# design.net
KiCad netlist of a schematic drawn in Altium Designer
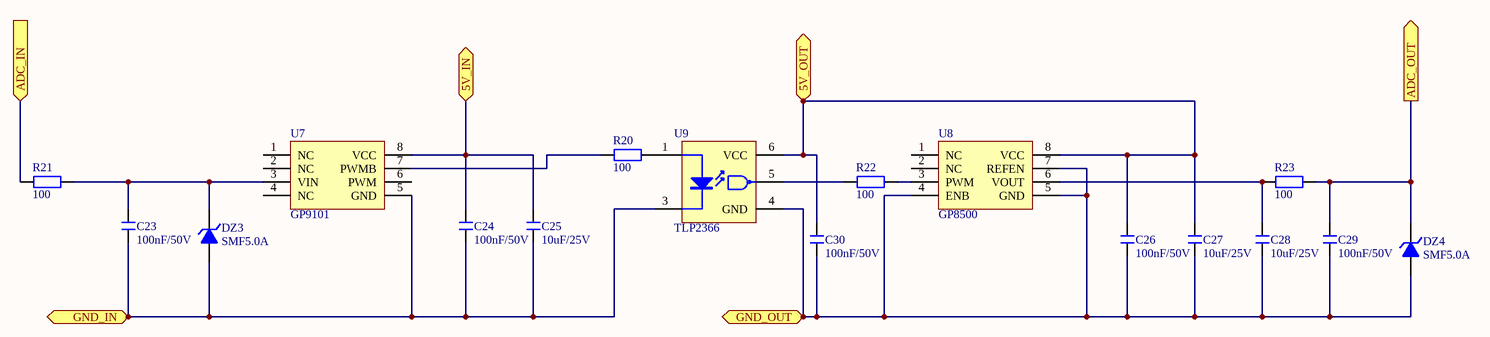
[diagram p0: 第二路电压隔离原理图.SchDoc]

(export (version "E")
  (design (tool "Eeschema 10.0.6"))
  (components
    (comp (ref "C23")
      (value "100nF/50V")
      (footprint "C 0603_M")
      (description "无极性贴片电容")
      (fields (field (name "版权归属") "源创客"))
      (libsource (lib "3.1   - 电阻-电容-电感") (part "C"))
    )
    (comp (ref "C24")
      (value "100nF/50V")
      (footprint "C 0603_M")
      (description "无极性贴片电容")
      (fields (field (name "版权归属") "源创客"))
      (libsource (lib "3.1   - 电阻-电容-电感") (part "C"))
    )
    (comp (ref "C25")
      (value "10uF/25V")
      (footprint "C 0603_M")
      (description "无极性贴片电容")
      (fields (field (name "版权归属") "源创客"))
      (libsource (lib "3.1   - 电阻-电容-电感") (part "C"))
    )
    (comp (ref "C26")
      (value "100nF/50V")
      (footprint "C 0603_M")
      (description "无极性贴片电容")
      (fields (field (name "版权归属") "源创客"))
      (libsource (lib "3.1   - 电阻-电容-电感") (part "C"))
    )
    (comp (ref "C27")
      (value "10uF/25V")
      (footprint "C 0603_M")
      (description "无极性贴片电容")
      (fields (field (name "版权归属") "源创客"))
      (libsource (lib "3.1   - 电阻-电容-电感") (part "C"))
    )
    (comp (ref "C28")
      (value "10uF/25V")
      (footprint "C 0603_M")
      (description "无极性贴片电容")
      (fields (field (name "版权归属") "源创客"))
      (libsource (lib "3.1   - 电阻-电容-电感") (part "C"))
    )
    (comp (ref "C29")
      (value "100nF/50V")
      (footprint "C 0603_M")
      (description "无极性贴片电容")
      (fields (field (name "版权归属") "源创客"))
      (libsource (lib "3.1   - 电阻-电容-电感") (part "C"))
    )
    (comp (ref "C30")
      (value "100nF/50V")
      (footprint "C 0603_M")
      (description "无极性贴片电容")
      (fields (field (name "版权归属") "源创客"))
      (libsource (lib "3.1   - 电阻-电容-电感") (part "C"))
    )
    (comp (ref "DZ3")
      (value "SMF5.0A")
      (footprint "SOD-123")
      (description "3.3V/0.5W稳压管")
      (fields (field (name "版权归属") "源创客"))
      (libsource (lib "8.1   - 二极管-整流桥") (part "1N4620"))
    )
    (comp (ref "DZ4")
      (value "SMF5.0A")
      (footprint "SOD-123")
      (description "3.3V/0.5W稳压管")
      (fields (field (name "版权归属") "源创客"))
      (libsource (lib "8.1   - 二极管-整流桥") (part "1N4620"))
    )
    (comp (ref "R20")
      (value "100")
      (footprint "R 0603_M")
      (description "贴片电阻")
      (fields (field (name "版权归属") "源创客"))
      (libsource (lib "3.1   - 电阻-电容-电感") (part "R"))
    )
    (comp (ref "R21")
      (value "100")
      (footprint "R 0603_M")
      (description "贴片电阻")
      (fields (field (name "版权归属") "源创客"))
      (libsource (lib "3.1   - 电阻-电容-电感") (part "R"))
    )
    (comp (ref "R22")
      (value "100")
      (footprint "R 0603_M")
      (description "贴片电阻")
      (fields (field (name "版权归属") "源创客"))
      (libsource (lib "3.1   - 电阻-电容-电感") (part "R"))
    )
    (comp (ref "R23")
      (value "100")
      (footprint "R 0603_M")
      (description "贴片电阻")
      (fields (field (name "版权归属") "源创客"))
      (libsource (lib "3.1   - 电阻-电容-电感") (part "R"))
    )
    (comp (ref "U7")
      (value "GP9101")
      (footprint "SOP8_N")
      (description "将0V到VCC的模拟电压输入，线性转换成0%-100%占  空比的PWM信号输出")
      (libsource (lib "1.1   - IC芯片") (part "GP9101"))
    )
    (comp (ref "U8")
      (value "GP8500")
      (footprint "SOP8_N")
      (description "0%-100% PWM 转 0-2.5V/0-VCC")
      (libsource (lib "1.1   - IC芯片") (part "GP8500"))
    )
    (comp (ref "U9")
      (value "TLP2366")
      (footprint "SOP5_N")
      (description "单路高速光耦")
      (libsource (lib "11.1 - 传感元件") (part "TLP2366"))
    )
  )
  (nets
    (net (code "1") (name "/5V_IN") (class "Default")
      (node (ref "C24") (pin "2") (pinfunction "2_2") (pintype "passive"))
      (node (ref "C25") (pin "2") (pinfunction "2_2") (pintype "passive"))
      (node (ref "U7") (pin "8") (pinfunction "VCC_8") (pintype "passive"))
    )
    (net (code "2") (name "/5V_OUT") (class "Default")
      (node (ref "C26") (pin "2") (pinfunction "2_2") (pintype "passive"))
      (node (ref "C27") (pin "2") (pinfunction "2_2") (pintype "passive"))
      (node (ref "C30") (pin "2") (pinfunction "2_2") (pintype "passive"))
      (node (ref "U8") (pin "8") (pinfunction "VCC_8") (pintype "passive"))
      (node (ref "U9") (pin "6") (pinfunction "VCC_6") (pintype "passive"))
    )
    (net (code "3") (name "/ADC_IN") (class "Default")
      (node (ref "R21") (pin "1") (pinfunction "1_1") (pintype "passive"))
    )
    (net (code "4") (name "/ADC_OUT") (class "Default")
      (node (ref "C29") (pin "2") (pinfunction "2_2") (pintype "passive"))
      (node (ref "DZ4") (pin "2") (pinfunction "K_2") (pintype "passive"))
      (node (ref "R23") (pin "2") (pinfunction "2_2") (pintype "passive"))
    )
    (net (code "5") (name "/GND_IN") (class "Default")
      (node (ref "C23") (pin "1") (pinfunction "1_1") (pintype "passive"))
      (node (ref "C24") (pin "1") (pinfunction "1_1") (pintype "passive"))
      (node (ref "C25") (pin "1") (pinfunction "1_1") (pintype "passive"))
      (node (ref "DZ3") (pin "1") (pinfunction "A_1") (pintype "passive"))
      (node (ref "U7") (pin "5") (pinfunction "GND_5") (pintype "passive"))
      (node (ref "U9") (pin "3") (pinfunction "LED-_3") (pintype "passive"))
    )
    (net (code "6") (name "/GND_OUT") (class "Default")
      (node (ref "C26") (pin "1") (pinfunction "1_1") (pintype "passive"))
      (node (ref "C27") (pin "1") (pinfunction "1_1") (pintype "passive"))
      (node (ref "C28") (pin "1") (pinfunction "1_1") (pintype "passive"))
      (node (ref "C29") (pin "1") (pinfunction "1_1") (pintype "passive"))
      (node (ref "C30") (pin "1") (pinfunction "1_1") (pintype "passive"))
      (node (ref "DZ4") (pin "1") (pinfunction "A_1") (pintype "passive"))
      (node (ref "U8") (pin "4") (pinfunction "ENB_4") (pintype "passive"))
      (node (ref "U8") (pin "5") (pinfunction "GND_5") (pintype "passive"))
      (node (ref "U8") (pin "7") (pinfunction "REFEN_7") (pintype "passive"))
      (node (ref "U9") (pin "4") (pinfunction "GND_4") (pintype "passive"))
    )
    (net (code "7") (name "Net-(DZ3-K)") (class "Default")
      (node (ref "C23") (pin "2") (pinfunction "2_2") (pintype "passive"))
      (node (ref "DZ3") (pin "2") (pinfunction "K_2") (pintype "passive"))
      (node (ref "R21") (pin "2") (pinfunction "2_2") (pintype "passive"))
      (node (ref "U7") (pin "3") (pinfunction "VIN_3") (pintype "passive"))
    )
    (net (code "8") (name "Net-(R22-Pad1)") (class "Default")
      (node (ref "R22") (pin "1") (pinfunction "1_1") (pintype "passive"))
      (node (ref "U9") (pin "5") (pinfunction "GND_5") (pintype "passive"))
    )
    (net (code "9") (name "Net-(U7-PWMB)") (class "Default")
      (node (ref "R20") (pin "1") (pinfunction "1_1") (pintype "passive"))
      (node (ref "U7") (pin "7") (pinfunction "PWMB_7") (pintype "passive"))
    )
    (net (code "10") (name "Net-(U8-PWM)") (class "Default")
      (node (ref "R22") (pin "2") (pinfunction "2_2") (pintype "passive"))
      (node (ref "U8") (pin "3") (pinfunction "PWM_3") (pintype "passive"))
    )
    (net (code "11") (name "Net-(U8-VOUT)") (class "Default")
      (node (ref "C28") (pin "2") (pinfunction "2_2") (pintype "passive"))
      (node (ref "R23") (pin "1") (pinfunction "1_1") (pintype "passive"))
      (node (ref "U8") (pin "6") (pinfunction "VOUT_6") (pintype "passive"))
    )
    (net (code "12") (name "Net-(U9-LED+)") (class "Default")
      (node (ref "R20") (pin "2") (pinfunction "2_2") (pintype "passive"))
      (node (ref "U9") (pin "1") (pinfunction "LED+_1") (pintype "passive"))
    )
    (net (code "13") (name "unconnected-(U7-NC-Pad1)") (class "Default")
      (node (ref "U7") (pin "1") (pinfunction "NC_1") (pintype "passive"))
    )
    (net (code "14") (name "unconnected-(U7-NC-Pad2)") (class "Default")
      (node (ref "U7") (pin "2") (pinfunction "NC_2") (pintype "passive"))
    )
    (net (code "15") (name "unconnected-(U7-NC-Pad4)") (class "Default")
      (node (ref "U7") (pin "4") (pinfunction "NC_4") (pintype "passive"))
    )
    (net (code "16") (name "unconnected-(U7-PWM-Pad6)") (class "Default")
      (node (ref "U7") (pin "6") (pinfunction "PWM_6") (pintype "passive"))
    )
    (net (code "17") (name "unconnected-(U8-NC-Pad1)") (class "Default")
      (node (ref "U8") (pin "1") (pinfunction "NC_1") (pintype "passive"))
    )
    (net (code "18") (name "unconnected-(U8-NC-Pad2)") (class "Default")
      (node (ref "U8") (pin "2") (pinfunction "NC_2") (pintype "passive"))
    )
  )
)
